# gps_sensor.net
KiCad netlist of a schematic drawn in EAGLE
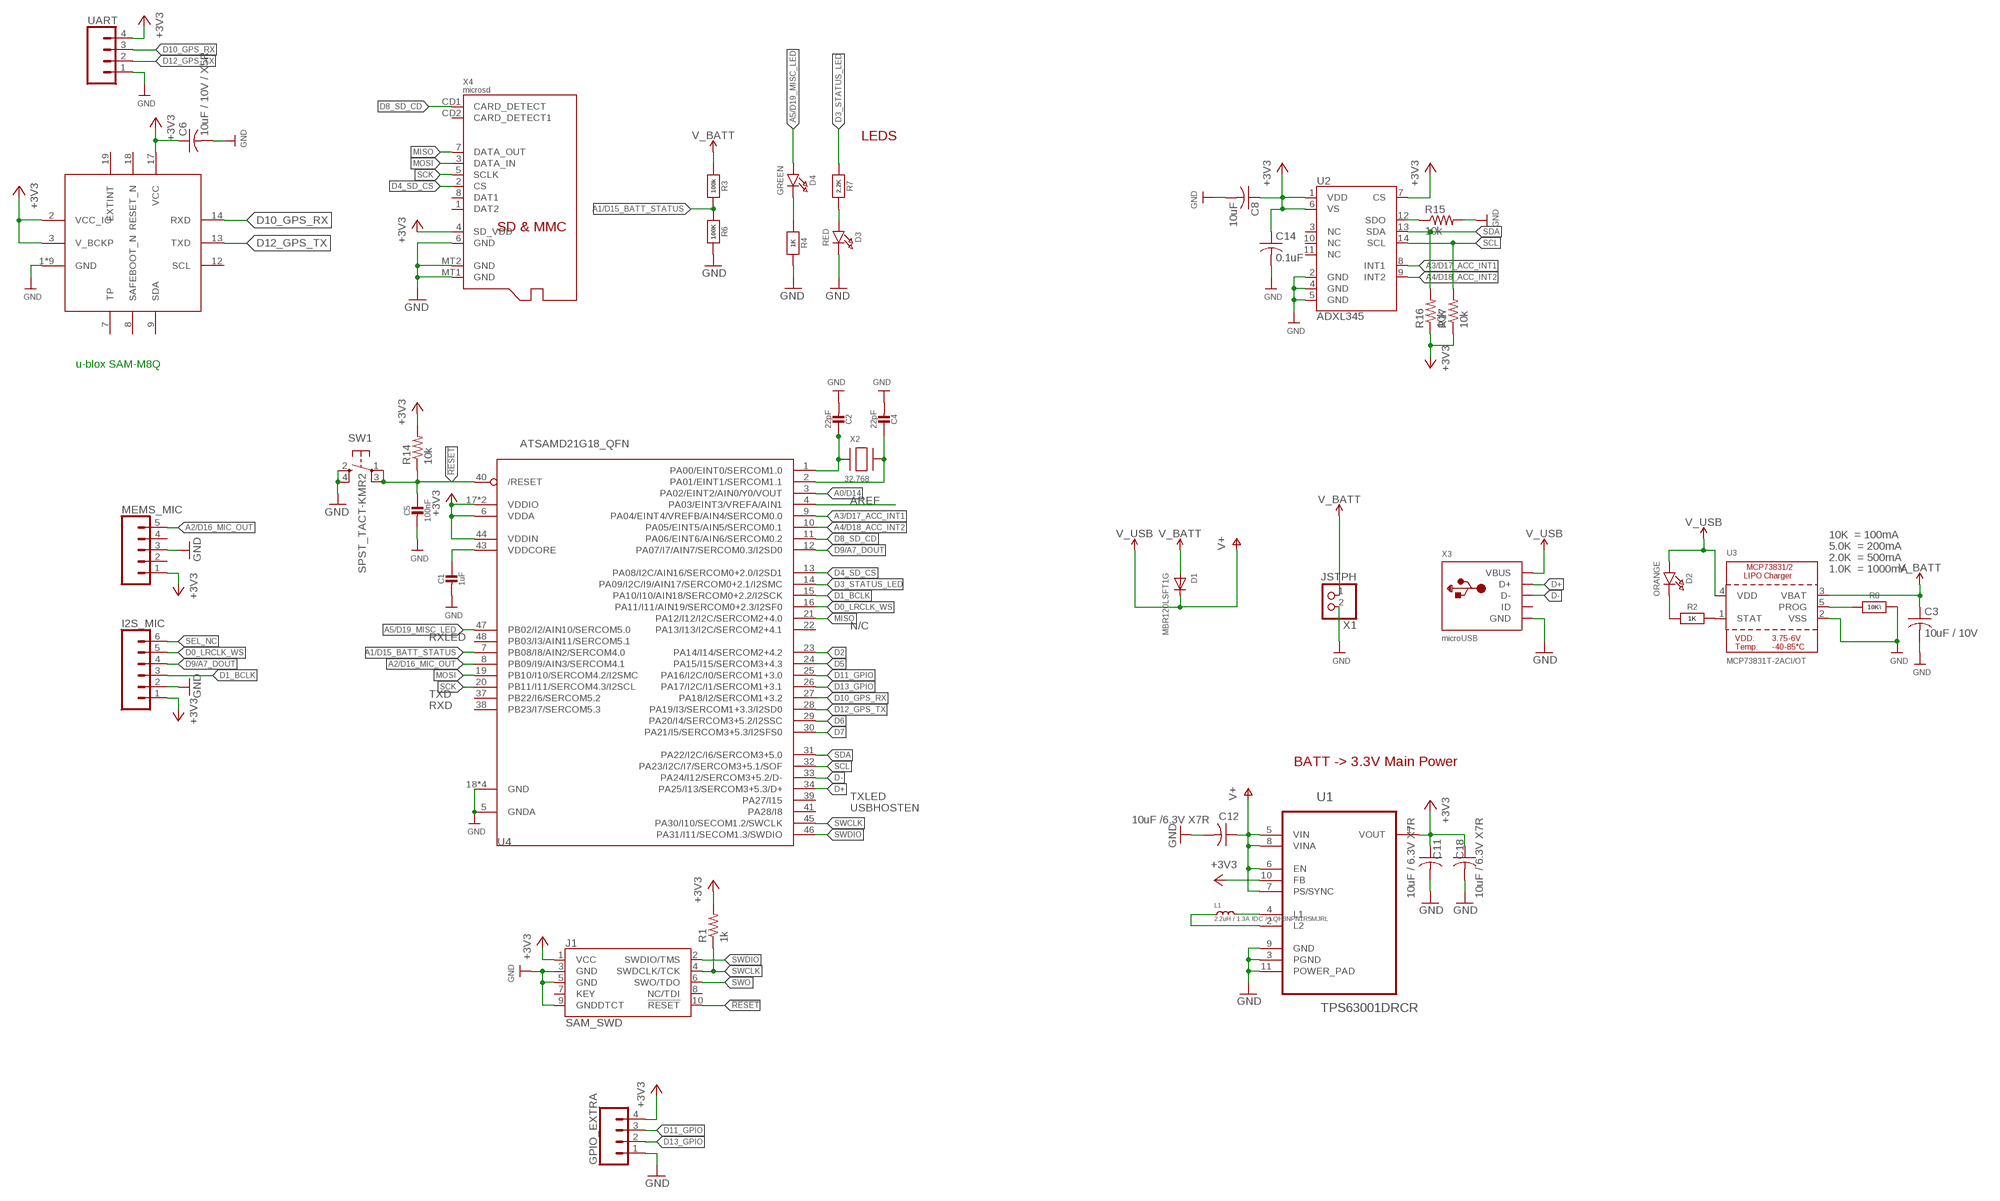
[diagram p0: schematic, sheet 1]

(export (version "E")
  (design (tool "Eeschema 10.0.6"))
  (components
    (comp (ref "C1")
      (value "1uF")
      (footprint "eagle-import:0603-NO")
      (libsource (lib "eagle-import") (part "CAP_CERAMIC0603_NO"))
    )
    (comp (ref "C2")
      (value "22pF")
      (footprint "eagle-import:0603-NO")
      (libsource (lib "eagle-import") (part "CAP_CERAMIC0603_NO"))
    )
    (comp (ref "C3")
      (value "10uF / 10V")
      (footprint "eagle-import:C0603")
      (libsource (lib "eagle-import") (part "C-USC0603"))
    )
    (comp (ref "C4")
      (value "22pF")
      (footprint "eagle-import:0603-NO")
      (libsource (lib "eagle-import") (part "CAP_CERAMIC0603_NO"))
    )
    (comp (ref "C5")
      (value "100nF")
      (footprint "eagle-import:0603-NO")
      (libsource (lib "eagle-import") (part "CAP_CERAMIC0603_NO"))
    )
    (comp (ref "C6")
      (value "10uF / 10V / X5R")
      (footprint "eagle-import:C0603")
      (libsource (lib "eagle-import") (part "C-USC0603"))
    )
    (comp (ref "C8")
      (value "10uF")
      (footprint "eagle-import:C0603")
      (libsource (lib "eagle-import") (part "C-USC0603"))
    )
    (comp (ref "C11")
      (value "10uF / 6.3V X7R")
      (footprint "eagle-import:C0603")
      (libsource (lib "eagle-import") (part "C-USC0603"))
    )
    (comp (ref "C12")
      (value "10uF /6.3V X7R")
      (footprint "eagle-import:C0603")
      (libsource (lib "eagle-import") (part "C-USC0603"))
    )
    (comp (ref "C14")
      (value "0.1uF")
      (footprint "eagle-import:C0603")
      (libsource (lib "eagle-import") (part "C-USC0603"))
    )
    (comp (ref "C18")
      (value "10uF / 6.3V X7R")
      (footprint "eagle-import:C0603")
      (libsource (lib "eagle-import") (part "C-USC0603"))
    )
    (comp (ref "D1")
      (value "MBR120LSFT1G")
      (footprint "eagle-import:SOD-123FL")
      (libsource (lib "eagle-import") (part "DIODE_SOD-123FL"))
    )
    (comp (ref "D2")
      (value "ORANGE")
      (footprint "eagle-import:CHIPLED_0805_NOOUTLINE")
      (libsource (lib "eagle-import") (part "LED0805_NOOUTLINE"))
    )
    (comp (ref "D3")
      (value "RED")
      (footprint "eagle-import:CHIPLED_0805_NOOUTLINE")
      (libsource (lib "eagle-import") (part "LED0805_NOOUTLINE"))
    )
    (comp (ref "D4")
      (value "GREEN")
      (footprint "eagle-import:CHIPLED_0805_NOOUTLINE")
      (libsource (lib "eagle-import") (part "LED0805_NOOUTLINE"))
    )
    (comp (ref "GPIO_EXTRA")
      (value "CONN_04")
      (footprint "eagle-import:1X04")
      (libsource (lib "eagle-import") (part "CONN_04"))
    )
    (comp (ref "I2S_MIC")
      (value "CONN_06NO_SILK_NO_POP")
      (footprint "eagle-import:1X06_NO_SILK")
      (libsource (lib "eagle-import") (part "CONN_06NO_SILK_NO_POP"))
    )
    (comp (ref "J1")
      (value "SAM_SWD")
      (footprint "eagle-import:SAMTECH_FTSH-105-01")
      (libsource (lib "eagle-import") (part "CORTEX_DEBUG_SMD"))
    )
    (comp (ref "L1")
      (value "2.2uH / 1.3A IDC / LQH3NPN1R5MJRL")
      (footprint "eagle-import:LQH3NP_M0")
      (libsource (lib "eagle-import") (part "LQH3NPN___MM0"))
    )
    (comp (ref "MEMS_MIC")
      (value "CONN_05")
      (footprint "eagle-import:1X05")
      (libsource (lib "eagle-import") (part "CONN_05"))
    )
    (comp (ref "R1")
      (value "1k")
      (footprint "eagle-import:R0603")
      (libsource (lib "eagle-import") (part "R-US_R0603"))
    )
    (comp (ref "R2")
      (value "1K")
      (footprint "eagle-import:0603-NO")
      (libsource (lib "eagle-import") (part "RESISTOR_0603_NOOUT"))
    )
    (comp (ref "R3")
      (value "100k")
      (footprint "eagle-import:0603-NO")
      (libsource (lib "eagle-import") (part "RESISTOR_0603_NOOUT"))
    )
    (comp (ref "R4")
      (value "1K")
      (footprint "eagle-import:0603-NO")
      (libsource (lib "eagle-import") (part "RESISTOR_0603_NOOUT"))
    )
    (comp (ref "R6")
      (value "100K")
      (footprint "eagle-import:0603-NO")
      (libsource (lib "eagle-import") (part "RESISTOR_0603_NOOUT"))
    )
    (comp (ref "R7")
      (value "2.2K")
      (footprint "eagle-import:0603-NO")
      (libsource (lib "eagle-import") (part "RESISTOR_0603_NOOUT"))
    )
    (comp (ref "R8")
      (value "10K\\")
      (footprint "eagle-import:0603-NO")
      (libsource (lib "eagle-import") (part "RESISTOR_0603_NOOUT"))
    )
    (comp (ref "R14")
      (value "10k")
      (footprint "eagle-import:R0603")
      (libsource (lib "eagle-import") (part "R-US_R0603"))
    )
    (comp (ref "R15")
      (value "10k")
      (footprint "eagle-import:R0603")
      (libsource (lib "eagle-import") (part "R-US_R0603"))
    )
    (comp (ref "R16")
      (value "10k")
      (footprint "eagle-import:R0603")
      (libsource (lib "eagle-import") (part "R-US_R0603"))
    )
    (comp (ref "R17")
      (value "10k")
      (footprint "eagle-import:R0603")
      (libsource (lib "eagle-import") (part "R-US_R0603"))
    )
    (comp (ref "SW1")
      (value "SPST_TACT-KMR2")
      (footprint "eagle-import:KMR2")
      (libsource (lib "eagle-import") (part "SPST_TACT-KMR2"))
    )
    (comp (ref "U1")
      (value "TPS63001DRCR")
      (footprint "eagle-import:SON50P300X300X100-11N")
      (libsource (lib "eagle-import") (part "TPS63001DRCR"))
    )
    (comp (ref "U2")
      (value "ADXL345")
      (footprint "eagle-import:LGA-14")
      (libsource (lib "eagle-import") (part "ADXL345"))
    )
    (comp (ref "U3")
      (value "MCP73831T-2ACI/OT")
      (footprint "eagle-import:SOT23-5")
      (libsource (lib "eagle-import") (part "MCP73831/2"))
    )
    (comp (ref "U4")
      (value "ATSAMD21G18_QFN")
      (footprint "eagle-import:TQFN48_7MM")
      (libsource (lib "eagle-import") (part "ATSAMD21J_QFN"))
    )
    (comp (ref "U5")
      (value "SAM-M8Q")
      (footprint "eagle-import:SAM-M8Q")
      (libsource (lib "eagle-import") (part "SAM-M8Q"))
    )
    (comp (ref "UART")
      (value "CONN_041X04_NO_SILK")
      (footprint "eagle-import:1X04_NO_SILK")
      (libsource (lib "eagle-import") (part "CONN_041X04_NO_SILK"))
    )
    (comp (ref "X1")
      (value "JSTPH")
      (footprint "eagle-import:JST-PH-2-SMT-RA")
      (libsource (lib "eagle-import") (part "JST_2PIN-SMT-RA"))
    )
    (comp (ref "X2")
      (value "32.768")
      (footprint "eagle-import:XTAL3215")
      (libsource (lib "eagle-import") (part "XTAL-3.2X1.5"))
    )
    (comp (ref "X3")
      (value "microUSB")
      (footprint "eagle-import:4UCONN_20329_V2")
      (libsource (lib "eagle-import") (part "USB_MICRO_20329_V2"))
    )
    (comp (ref "X4")
      (value "microsd")
      (footprint "eagle-import:MICROSD")
      (libsource (lib "eagle-import") (part "MICROSD"))
    )
  )
  (nets
    (net (code "1") (name "+3V3") (class "Default")
      (node (ref "C11") (pin "1") (pinfunction "1_1") (pintype "passive"))
      (node (ref "C14") (pin "1") (pinfunction "1_1") (pintype "passive"))
      (node (ref "C18") (pin "1") (pinfunction "1_1") (pintype "passive"))
      (node (ref "C6") (pin "1") (pinfunction "1_1") (pintype "passive"))
      (node (ref "C8") (pin "1") (pinfunction "1_1") (pintype "passive"))
      (node (ref "GPIO_EXTRA") (pin "4") (pinfunction "4_4") (pintype "passive"))
      (node (ref "I2S_MIC") (pin "1") (pinfunction "1_1") (pintype "passive"))
      (node (ref "J1") (pin "1") (pinfunction "VCC_1") (pintype "bidirectional"))
      (node (ref "MEMS_MIC") (pin "1") (pinfunction "1_1") (pintype "passive"))
      (node (ref "R1") (pin "2") (pinfunction "2_2") (pintype "passive"))
      (node (ref "R14") (pin "2") (pinfunction "2_2") (pintype "passive"))
      (node (ref "R16") (pin "1") (pinfunction "1_1") (pintype "passive"))
      (node (ref "R17") (pin "1") (pinfunction "1_1") (pintype "passive"))
      (node (ref "U1") (pin "1") (pinfunction "VOUT_1") (pintype "output"))
      (node (ref "U1") (pin "10") (pinfunction "FB_10") (pintype "input"))
      (node (ref "U2") (pin "1") (pinfunction "VDD_1") (pintype "bidirectional"))
      (node (ref "U2") (pin "6") (pinfunction "VS_6") (pintype "bidirectional"))
      (node (ref "U2") (pin "7") (pinfunction "CS_7") (pintype "bidirectional"))
      (node (ref "U4") (pin "17") (pinfunction "VDDIO_17") (pintype "power_in"))
      (node (ref "U4") (pin "36") (pinfunction "VDDIO_36") (pintype "power_in"))
      (node (ref "U4") (pin "44") (pinfunction "VDDIN_44") (pintype "power_in"))
      (node (ref "U4") (pin "6") (pinfunction "VDDA_6") (pintype "power_in"))
      (node (ref "U5") (pin "17") (pinfunction "VCC_17") (pintype "bidirectional"))
      (node (ref "U5") (pin "2") (pinfunction "VCC_IO_2") (pintype "bidirectional"))
      (node (ref "U5") (pin "3") (pinfunction "V_BCKP_3") (pintype "bidirectional"))
      (node (ref "UART") (pin "4") (pinfunction "4_4") (pintype "passive"))
      (node (ref "X4") (pin "4") (pinfunction "SD_VDD_4") (pintype "power_in"))
    )
    (net (code "2") (name "/AREF") (class "Default")
      (node (ref "U4") (pin "4") (pinfunction "PA03/EINT3/VREFA/AIN1_4") (pintype "bidirectional"))
    )
    (net (code "3") (name "/~{RESET}") (class "Default")
      (node (ref "C5") (pin "1") (pinfunction "1_1") (pintype "passive"))
      (node (ref "J1") (pin "10") (pinfunction "~{RESET}_10") (pintype "bidirectional"))
      (node (ref "R14") (pin "1") (pinfunction "1_1") (pintype "passive"))
      (node (ref "SW1") (pin "1") (pinfunction "P_1") (pintype "passive"))
      (node (ref "SW1") (pin "3") (pinfunction "P1_3") (pintype "passive"))
      (node (ref "U4") (pin "40") (pinfunction "/RESET_40") (pintype "bidirectional"))
    )
    (net (code "4") (name "A0{slash}D14") (class "Default")
      (node (ref "U4") (pin "3") (pinfunction "PA02/EINT2/AIN0/Y0/VOUT_3") (pintype "bidirectional"))
    )
    (net (code "5") (name "A1{slash}D15_BATT_STATUS") (class "Default")
      (node (ref "R3") (pin "2") (pinfunction "2_2") (pintype "passive"))
      (node (ref "R6") (pin "1") (pinfunction "1_1") (pintype "passive"))
      (node (ref "U4") (pin "7") (pinfunction "PB08/I8/AIN2/SERCOM4.0_7") (pintype "bidirectional"))
    )
    (net (code "6") (name "A2{slash}D16_MIC_OUT") (class "Default")
      (node (ref "MEMS_MIC") (pin "5") (pinfunction "5_5") (pintype "passive"))
      (node (ref "U4") (pin "8") (pinfunction "PB09/I9/AIN3/SERCOM4.1_8") (pintype "bidirectional"))
    )
    (net (code "7") (name "A3{slash}D17_ACC_INT1") (class "Default")
      (node (ref "U2") (pin "8") (pinfunction "INT1_8") (pintype "bidirectional"))
      (node (ref "U4") (pin "9") (pinfunction "PA04/EINT4/VREFB/AIN4/SERCOM0.0_9") (pintype "bidirectional"))
    )
    (net (code "8") (name "A4{slash}D18_ACC_INT2") (class "Default")
      (node (ref "U2") (pin "9") (pinfunction "INT2_9") (pintype "bidirectional"))
      (node (ref "U4") (pin "10") (pinfunction "PA05/EINT5/AIN5/SERCOM0.1_10") (pintype "bidirectional"))
    )
    (net (code "9") (name "A5{slash}D19_MISC_LED") (class "Default")
      (node (ref "D4") (pin "A") (pinfunction "A_A") (pintype "passive"))
      (node (ref "U4") (pin "47") (pinfunction "PB02/I2/AIN10/SERCOM5.0_47") (pintype "bidirectional"))
    )
    (net (code "10") (name "D+") (class "Default")
      (node (ref "U4") (pin "34") (pinfunction "PA25/I13/SERCOM3+5.3/D+_34") (pintype "bidirectional"))
      (node (ref "X3") (pin "D+") (pinfunction "D+_D+") (pintype "bidirectional"))
    )
    (net (code "11") (name "D-") (class "Default")
      (node (ref "U4") (pin "33") (pinfunction "PA24/I12/SERCOM3+5.2/D-_33") (pintype "bidirectional"))
      (node (ref "X3") (pin "D-") (pinfunction "D-_D-") (pintype "bidirectional"))
    )
    (net (code "12") (name "D0_LRCLK_WS") (class "Default")
      (node (ref "I2S_MIC") (pin "5") (pinfunction "5_5") (pintype "passive"))
      (node (ref "U4") (pin "16") (pinfunction "PA11/I11/AIN19/SERCOM0+2.3/I2SF0_16") (pintype "bidirectional"))
    )
    (net (code "13") (name "D1_BCLK") (class "Default")
      (node (ref "I2S_MIC") (pin "3") (pinfunction "3_3") (pintype "passive"))
      (node (ref "U4") (pin "15") (pinfunction "PA10/I10/AIN18/SERCOM0+2.2/I2SCK_15") (pintype "bidirectional"))
    )
    (net (code "14") (name "D2") (class "Default")
      (node (ref "U4") (pin "23") (pinfunction "PA14/I14/SERCOM2+4.2_23") (pintype "bidirectional"))
    )
    (net (code "15") (name "D3_STATUS_LED") (class "Default")
      (node (ref "R7") (pin "1") (pinfunction "1_1") (pintype "passive"))
      (node (ref "U4") (pin "14") (pinfunction "PA09/I2C/I9/AIN17/SERCOM0+2.1/I2SMC_14") (pintype "bidirectional"))
    )
    (net (code "16") (name "D4_SD_CS") (class "Default")
      (node (ref "U4") (pin "13") (pinfunction "PA08/I2C/AIN16/SERCOM0+2.0/I2SD1_13") (pintype "bidirectional"))
      (node (ref "X4") (pin "2") (pinfunction "CS_2") (pintype "input"))
    )
    (net (code "17") (name "D5") (class "Default")
      (node (ref "U4") (pin "24") (pinfunction "PA15/I15/SERCOM3+4.3_24") (pintype "bidirectional"))
    )
    (net (code "18") (name "D6") (class "Default")
      (node (ref "U4") (pin "29") (pinfunction "PA20/I4/SERCOM3+5.2/I2SSC_29") (pintype "bidirectional"))
    )
    (net (code "19") (name "D7") (class "Default")
      (node (ref "U4") (pin "30") (pinfunction "PA21/I5/SERCOM3+5.3/I2SFS0_30") (pintype "bidirectional"))
    )
    (net (code "20") (name "D8_SD_CD") (class "Default")
      (node (ref "U4") (pin "11") (pinfunction "PA06/EINT6/AIN6/SERCOM0.2_11") (pintype "bidirectional"))
      (node (ref "X4") (pin "CD1") (pinfunction "CARD_DETECT_CD1") (pintype "passive"))
    )
    (net (code "21") (name "D9{slash}A7_DOUT") (class "Default")
      (node (ref "I2S_MIC") (pin "4") (pinfunction "4_4") (pintype "passive"))
      (node (ref "U4") (pin "12") (pinfunction "PA07/I7/AIN7/SERCOM0.3/I2SD0_12") (pintype "bidirectional"))
    )
    (net (code "22") (name "D10_GPS_RX") (class "Default")
      (node (ref "U4") (pin "27") (pinfunction "PA18/I2/SERCOM1+3.2_27") (pintype "bidirectional"))
      (node (ref "U5") (pin "14") (pinfunction "RXD_14") (pintype "bidirectional"))
      (node (ref "UART") (pin "3") (pinfunction "3_3") (pintype "passive"))
    )
    (net (code "23") (name "D11_GPIO") (class "Default")
      (node (ref "GPIO_EXTRA") (pin "3") (pinfunction "3_3") (pintype "passive"))
      (node (ref "U4") (pin "25") (pinfunction "PA16/I2C/I0/SERCOM1+3.0_25") (pintype "bidirectional"))
    )
    (net (code "24") (name "D12_GPS_TX") (class "Default")
      (node (ref "U4") (pin "28") (pinfunction "PA19/I3/SERCOM1+3.3/I2SD0_28") (pintype "bidirectional"))
      (node (ref "U5") (pin "13") (pinfunction "TXD_13") (pintype "bidirectional"))
      (node (ref "UART") (pin "2") (pinfunction "2_2") (pintype "passive"))
    )
    (net (code "25") (name "D13_GPIO") (class "Default")
      (node (ref "GPIO_EXTRA") (pin "2") (pinfunction "2_2") (pintype "passive"))
      (node (ref "U4") (pin "26") (pinfunction "PA17/I2C/I1/SERCOM1+3.1_26") (pintype "bidirectional"))
    )
    (net (code "26") (name "GND") (class "Default")
      (node (ref "C1") (pin "2") (pinfunction "2_2") (pintype "passive"))
      (node (ref "C11") (pin "2") (pinfunction "2_2") (pintype "passive"))
      (node (ref "C12") (pin "2") (pinfunction "2_2") (pintype "passive"))
      (node (ref "C14") (pin "2") (pinfunction "2_2") (pintype "passive"))
      (node (ref "C18") (pin "2") (pinfunction "2_2") (pintype "passive"))
      (node (ref "C2") (pin "2") (pinfunction "2_2") (pintype "passive"))
      (node (ref "C3") (pin "2") (pinfunction "2_2") (pintype "passive"))
      (node (ref "C4") (pin "2") (pinfunction "2_2") (pintype "passive"))
      (node (ref "C5") (pin "2") (pinfunction "2_2") (pintype "passive"))
      (node (ref "C6") (pin "2") (pinfunction "2_2") (pintype "passive"))
      (node (ref "C8") (pin "2") (pinfunction "2_2") (pintype "passive"))
      (node (ref "D3") (pin "C") (pinfunction "C_C") (pintype "passive"))
      (node (ref "GPIO_EXTRA") (pin "1") (pinfunction "1_1") (pintype "passive"))
      (node (ref "I2S_MIC") (pin "2") (pinfunction "2_2") (pintype "passive"))
      (node (ref "J1") (pin "3") (pinfunction "GND_3") (pintype "bidirectional"))
      (node (ref "J1") (pin "5") (pinfunction "GND_5") (pintype "bidirectional"))
      (node (ref "J1") (pin "9") (pinfunction "GNDDTCT_9") (pintype "bidirectional"))
      (node (ref "MEMS_MIC") (pin "3") (pinfunction "3_3") (pintype "passive"))
      (node (ref "R15") (pin "2") (pinfunction "2_2") (pintype "passive"))
      (node (ref "R4") (pin "2") (pinfunction "2_2") (pintype "passive"))
      (node (ref "R6") (pin "2") (pinfunction "2_2") (pintype "passive"))
      (node (ref "R8") (pin "2") (pinfunction "2_2") (pintype "passive"))
      (node (ref "SW1") (pin "2") (pinfunction "S_2") (pintype "passive"))
      (node (ref "SW1") (pin "4") (pinfunction "S1_4") (pintype "passive"))
      (node (ref "U1") (pin "11") (pinfunction "POWER_PAD_11") (pintype "passive"))
      (node (ref "U1") (pin "3") (pinfunction "PGND_3") (pintype "passive"))
      (node (ref "U1") (pin "9") (pinfunction "GND_9") (pintype "passive"))
      (node (ref "U2") (pin "2") (pinfunction "GND_2") (pintype "bidirectional"))
      (node (ref "U2") (pin "4") (pinfunction "GND_4") (pintype "bidirectional"))
      (node (ref "U2") (pin "5") (pinfunction "GND_5") (pintype "bidirectional"))
      (node (ref "U3") (pin "2") (pinfunction "VSS_2") (pintype "power_in"))
      (node (ref "U4") (pin "18") (pinfunction "GND_18") (pintype "power_in"))
      (node (ref "U4") (pin "35") (pinfunction "GND_35") (pintype "power_in"))
      (node (ref "U4") (pin "42") (pinfunction "GND_42") (pintype "power_in"))
      (node (ref "U4") (pin "5") (pinfunction "GNDA_5") (pintype "power_in"))
      (node (ref "U4") (pin "THERMAL") (pinfunction "GND_THERMAL") (pintype "power_in"))
      (node (ref "U5") (pin "1") (pinfunction "GND_1") (pintype "bidirectional"))
      (node (ref "U5") (pin "10") (pinfunction "GND_10") (pintype "bidirectional"))
      (node (ref "U5") (pin "11") (pinfunction "GND_11") (pintype "bidirectional"))
      (node (ref "U5") (pin "15") (pinfunction "GND_15") (pintype "bidirectional"))
      (node (ref "U5") (pin "16") (pinfunction "GND_16") (pintype "bidirectional"))
      (node (ref "U5") (pin "20") (pinfunction "GND_20") (pintype "bidirectional"))
      (node (ref "U5") (pin "4") (pinfunction "GND_4") (pintype "bidirectional"))
      (node (ref "U5") (pin "5") (pinfunction "GND_5") (pintype "bidirectional"))
      (node (ref "U5") (pin "6") (pinfunction "GND_6") (pintype "bidirectional"))
      (node (ref "UART") (pin "1") (pinfunction "1_1") (pintype "passive"))
      (node (ref "X1") (pin "2") (pinfunction "1_2") (pintype "passive"))
      (node (ref "X3") (pin "BASE@1") (pinfunction "GND_BASE@1") (pintype "power_in"))
      (node (ref "X3") (pin "BASE@2") (pinfunction "GND_BASE@2") (pintype "power_in"))
      (node (ref "X3") (pin "GND") (pinfunction "GND_GND") (pintype "power_in"))
      (node (ref "X3") (pin "SPRT@1") (pinfunction "GND_SPRT@1") (pintype "power_in"))
      (node (ref "X3") (pin "SPRT@2") (pinfunction "GND_SPRT@2") (pintype "power_in"))
      (node (ref "X3") (pin "SPRT@3") (pinfunction "GND_SPRT@3") (pintype "power_in"))
      (node (ref "X3") (pin "SPRT@4") (pinfunction "GND_SPRT@4") (pintype "power_in"))
      (node (ref "X4") (pin "6") (pinfunction "GND_6") (pintype "power_in"))
      (node (ref "X4") (pin "MT1") (pinfunction "GND_MT1") (pintype "power_in"))
      (node (ref "X4") (pin "MT2") (pinfunction "GND_MT2") (pintype "power_in"))
    )
    (net (code "27") (name "MISO") (class "Default")
      (node (ref "U4") (pin "21") (pinfunction "PA12/I12/I2C/SERCOM2+4.0_21") (pintype "bidirectional"))
      (node (ref "X4") (pin "7") (pinfunction "DATA_OUT_7") (pintype "output"))
    )
    (net (code "28") (name "MOSI") (class "Default")
      (node (ref "U4") (pin "19") (pinfunction "PB10/I10/SERCOM4.2/I2SMC_19") (pintype "bidirectional"))
      (node (ref "X4") (pin "3") (pinfunction "DATA_IN_3") (pintype "input"))
    )
    (net (code "29") (name "Net-(D2-PadC)") (class "Default")
      (node (ref "D2") (pin "C") (pinfunction "C_C") (pintype "passive"))
      (node (ref "R2") (pin "1") (pinfunction "1_1") (pintype "passive"))
    )
    (net (code "30") (name "Net-(D3-PadA)") (class "Default")
      (node (ref "D3") (pin "A") (pinfunction "A_A") (pintype "passive"))
      (node (ref "R7") (pin "2") (pinfunction "2_2") (pintype "passive"))
    )
    (net (code "31") (name "Net-(D4-PadC)") (class "Default")
      (node (ref "D4") (pin "C") (pinfunction "C_C") (pintype "passive"))
      (node (ref "R4") (pin "1") (pinfunction "1_1") (pintype "passive"))
    )
    (net (code "32") (name "Net-(U1-L1)") (class "Default")
      (node (ref "L1") (pin "2") (pinfunction "2_2") (pintype "passive"))
      (node (ref "U1") (pin "4") (pinfunction "L1_4") (pintype "passive"))
    )
    (net (code "33") (name "Net-(U1-L2)") (class "Default")
      (node (ref "L1") (pin "1") (pinfunction "1_1") (pintype "passive"))
      (node (ref "U1") (pin "2") (pinfunction "L2_2") (pintype "passive"))
    )
    (net (code "34") (name "Net-(U2-SDO)") (class "Default")
      (node (ref "R15") (pin "1") (pinfunction "1_1") (pintype "passive"))
      (node (ref "U2") (pin "12") (pinfunction "SDO_12") (pintype "bidirectional"))
    )
    (net (code "35") (name "Net-(U3-PROG)") (class "Default")
      (node (ref "R8") (pin "1") (pinfunction "1_1") (pintype "passive"))
      (node (ref "U3") (pin "5") (pinfunction "PROG_5") (pintype "input"))
    )
    (net (code "36") (name "Net-(U3-STAT)") (class "Default")
      (node (ref "R2") (pin "2") (pinfunction "2_2") (pintype "passive"))
      (node (ref "U3") (pin "1") (pinfunction "STAT_1") (pintype "output"))
    )
    (net (code "37") (name "Net-(U4-PA00{slash}EINT0{slash}SERCOM1.0)") (class "Default")
      (node (ref "C2") (pin "1") (pinfunction "1_1") (pintype "passive"))
      (node (ref "U4") (pin "1") (pinfunction "PA00/EINT0/SERCOM1.0_1") (pintype "bidirectional"))
      (node (ref "X2") (pin "P$1") (pinfunction "P$1_P$1") (pintype "bidirectional"))
    )
    (net (code "38") (name "Net-(U4-PA01{slash}EINT1{slash}SERCOM1.1)") (class "Default")
      (node (ref "C4") (pin "1") (pinfunction "1_1") (pintype "passive"))
      (node (ref "U4") (pin "2") (pinfunction "PA01/EINT1/SERCOM1.1_2") (pintype "bidirectional"))
      (node (ref "X2") (pin "P$2") (pinfunction "P$2_P$2") (pintype "bidirectional"))
    )
    (net (code "39") (name "Net-(U4-VDDCORE)") (class "Default")
      (node (ref "C1") (pin "1") (pinfunction "1_1") (pintype "passive"))
      (node (ref "U4") (pin "43") (pinfunction "VDDCORE_43") (pintype "power_in"))
    )
    (net (code "40") (name "SCK") (class "Default")
      (node (ref "U4") (pin "20") (pinfunction "PB11/I11/SERCOM4.3/I2SCL_20") (pintype "bidirectional"))
      (node (ref "X4") (pin "5") (pinfunction "SCLK_5") (pintype "input"))
    )
    (net (code "41") (name "SCL") (class "Default")
      (node (ref "R17") (pin "2") (pinfunction "2_2") (pintype "passive"))
      (node (ref "U2") (pin "14") (pinfunction "SCL_14") (pintype "bidirectional"))
      (node (ref "U4") (pin "32") (pinfunction "PA23/I2C/I7/SERCOM3+5.1/SOF_32") (pintype "bidirectional"))
    )
    (net (code "42") (name "SDA") (class "Default")
      (node (ref "R16") (pin "2") (pinfunction "2_2") (pintype "passive"))
      (node (ref "U2") (pin "13") (pinfunction "SDA_13") (pintype "bidirectional"))
      (node (ref "U4") (pin "31") (pinfunction "PA22/I2C/I6/SERCOM3+5.0_31") (pintype "bidirectional"))
    )
    (net (code "43") (name "SEL_NC") (class "Default")
      (node (ref "I2S_MIC") (pin "6") (pinfunction "6_6") (pintype "passive"))
    )
    (net (code "44") (name "SWCLK") (class "Default")
      (node (ref "J1") (pin "4") (pinfunction "SWDCLK/TCK_4") (pintype "bidirectional"))
      (node (ref "R1") (pin "1") (pinfunction "1_1") (pintype "passive"))
      (node (ref "U4") (pin "45") (pinfunction "PA30/I10/SECOM1.2/SWCLK_45") (pintype "bidirectional"))
    )
    (net (code "45") (name "SWDIO") (class "Default")
      (node (ref "J1") (pin "2") (pinfunction "SWDIO/TMS_2") (pintype "bidirectional"))
      (node (ref "U4") (pin "46") (pinfunction "PA31/I11/SECOM1.3/SWDIO_46") (pintype "bidirectional"))
    )
    (net (code "46") (name "SWO") (class "Default")
      (node (ref "J1") (pin "6") (pinfunction "SWO/TDO_6") (pintype "bidirectional"))
    )
    (net (code "47") (name "V+") (class "Default")
      (node (ref "C12") (pin "1") (pinfunction "1_1") (pintype "passive"))
      (node (ref "D1") (pin "C") (pinfunction "C_C") (pintype "passive"))
      (node (ref "D2") (pin "A") (pinfunction "A_A") (pintype "passive"))
      (node (ref "U1") (pin "5") (pinfunction "VIN_5") (pintype "power_in"))
      (node (ref "U1") (pin "6") (pinfunction "EN_6") (pintype "input"))
      (node (ref "U1") (pin "7") (pinfunction "PS/SYNC_7") (pintype "input"))
      (node (ref "U1") (pin "8") (pinfunction "VINA_8") (pintype "power_in"))
      (node (ref "U3") (pin "4") (pinfunction "VDD_4") (pintype "power_in"))
      (node (ref "X3") (pin "VBUS") (pinfunction "VBUS_VBUS") (pintype "power_in"))
    )
    (net (code "48") (name "V_BATT") (class "Default")
      (node (ref "C3") (pin "1") (pinfunction "1_1") (pintype "passive"))
      (node (ref "D1") (pin "A") (pinfunction "A_A") (pintype "passive"))
      (node (ref "R3") (pin "1") (pinfunction "1_1") (pintype "passive"))
      (node (ref "U3") (pin "3") (pinfunction "VBAT_3") (pintype "power_in"))
      (node (ref "X1") (pin "1") (pinfunction "2_1") (pintype "passive"))
    )
    (net (code "49") (name "unconnected-(J1-KEY-Pad7)") (class "Default")
      (node (ref "J1") (pin "7") (pinfunction "KEY_7") (pintype "bidirectional"))
    )
    (net (code "50") (name "unconnected-(J1-NC{slash}TDI-Pad8)") (class "Default")
      (node (ref "J1") (pin "8") (pinfunction "NC/TDI_8") (pintype "bidirectional"))
    )
    (net (code "51") (name "unconnected-(MEMS_MIC-Pad2)") (class "Default")
      (node (ref "MEMS_MIC") (pin "2") (pinfunction "2_2") (pintype "passive"))
    )
    (net (code "52") (name "unconnected-(MEMS_MIC-Pad4)") (class "Default")
      (node (ref "MEMS_MIC") (pin "4") (pinfunction "4_4") (pintype "passive"))
    )
    (net (code "53") (name "unconnected-(U2-NC-Pad3)") (class "Default")
      (node (ref "U2") (pin "3") (pinfunction "NC_3") (pintype "bidirectional"))
    )
    (net (code "54") (name "unconnected-(U2-NC-Pad10)") (class "Default")
      (node (ref "U2") (pin "10") (pinfunction "NC_10") (pintype "bidirectional"))
    )
    (net (code "55") (name "unconnected-(U2-NC-Pad11)") (class "Default")
      (node (ref "U2") (pin "11") (pinfunction "NC_11") (pintype "bidirectional"))
    )
    (net (code "56") (name "unconnected-(U4-PA13{slash}I13{slash}I2C{slash}SERCOM2+4.1-Pad22)") (class "Default")
      (node (ref "U4") (pin "22") (pinfunction "PA13/I13/I2C/SERCOM2+4.1_22") (pintype "bidirectional"))
    )
    (net (code "57") (name "unconnected-(U4-PA27{slash}I15-Pad39)") (class "Default")
      (node (ref "U4") (pin "39") (pinfunction "PA27/I15_39") (pintype "bidirectional"))
    )
    (net (code "58") (name "unconnected-(U4-PA28{slash}I8-Pad41)") (class "Default")
      (node (ref "U4") (pin "41") (pinfunction "PA28/I8_41") (pintype "bidirectional"))
    )
    (net (code "59") (name "unconnected-(U4-PB03{slash}I3{slash}AIN11{slash}SERCOM5.1-Pad48)") (class "Default")
      (node (ref "U4") (pin "48") (pinfunction "PB03/I3/AIN11/SERCOM5.1_48") (pintype "bidirectional"))
    )
    (net (code "60") (name "unconnected-(U4-PB22{slash}I6{slash}SERCOM5.2-Pad37)") (class "Default")
      (node (ref "U4") (pin "37") (pinfunction "PB22/I6/SERCOM5.2_37") (pintype "bidirectional"))
    )
    (net (code "61") (name "unconnected-(U4-PB23{slash}I7{slash}SERCOM5.3-Pad38)") (class "Default")
      (node (ref "U4") (pin "38") (pinfunction "PB23/I7/SERCOM5.3_38") (pintype "bidirectional"))
    )
    (net (code "62") (name "unconnected-(U5-EXTINT-Pad19)") (class "Default")
      (node (ref "U5") (pin "19") (pinfunction "EXTINT_19") (pintype "bidirectional"))
    )
    (net (code "63") (name "unconnected-(U5-RESET_N-Pad18)") (class "Default")
      (node (ref "U5") (pin "18") (pinfunction "RESET_N_18") (pintype "bidirectional"))
    )
    (net (code "64") (name "unconnected-(U5-SAFEBOOT_N-Pad8)") (class "Default")
      (node (ref "U5") (pin "8") (pinfunction "SAFEBOOT_N_8") (pintype "bidirectional"))
    )
    (net (code "65") (name "unconnected-(U5-SCL-Pad12)") (class "Default")
      (node (ref "U5") (pin "12") (pinfunction "SCL_12") (pintype "bidirectional"))
    )
    (net (code "66") (name "unconnected-(U5-SDA-Pad9)") (class "Default")
      (node (ref "U5") (pin "9") (pinfunction "SDA_9") (pintype "bidirectional"))
    )
    (net (code "67") (name "unconnected-(U5-TP-Pad7)") (class "Default")
      (node (ref "U5") (pin "7") (pinfunction "TP_7") (pintype "bidirectional"))
    )
    (net (code "68") (name "unconnected-(X3-PadID)") (class "Default")
      (node (ref "X3") (pin "ID") (pinfunction "ID_ID") (pintype "bidirectional"))
    )
    (net (code "69") (name "unconnected-(X4-CARD_DETECT1-PadCD2)") (class "Default")
      (node (ref "X4") (pin "CD2") (pinfunction "CARD_DETECT1_CD2") (pintype "passive"))
    )
    (net (code "70") (name "unconnected-(X4-DAT1-Pad8)") (class "Default")
      (node (ref "X4") (pin "8") (pinfunction "DAT1_8") (pintype "bidirectional"))
    )
    (net (code "71") (name "unconnected-(X4-DAT2-Pad1)") (class "Default")
      (node (ref "X4") (pin "1") (pinfunction "DAT2_1") (pintype "bidirectional"))
    )
  )
)
